# Frequency_Counter_v2.net
KiCad netlist of a schematic drawn in EAGLE
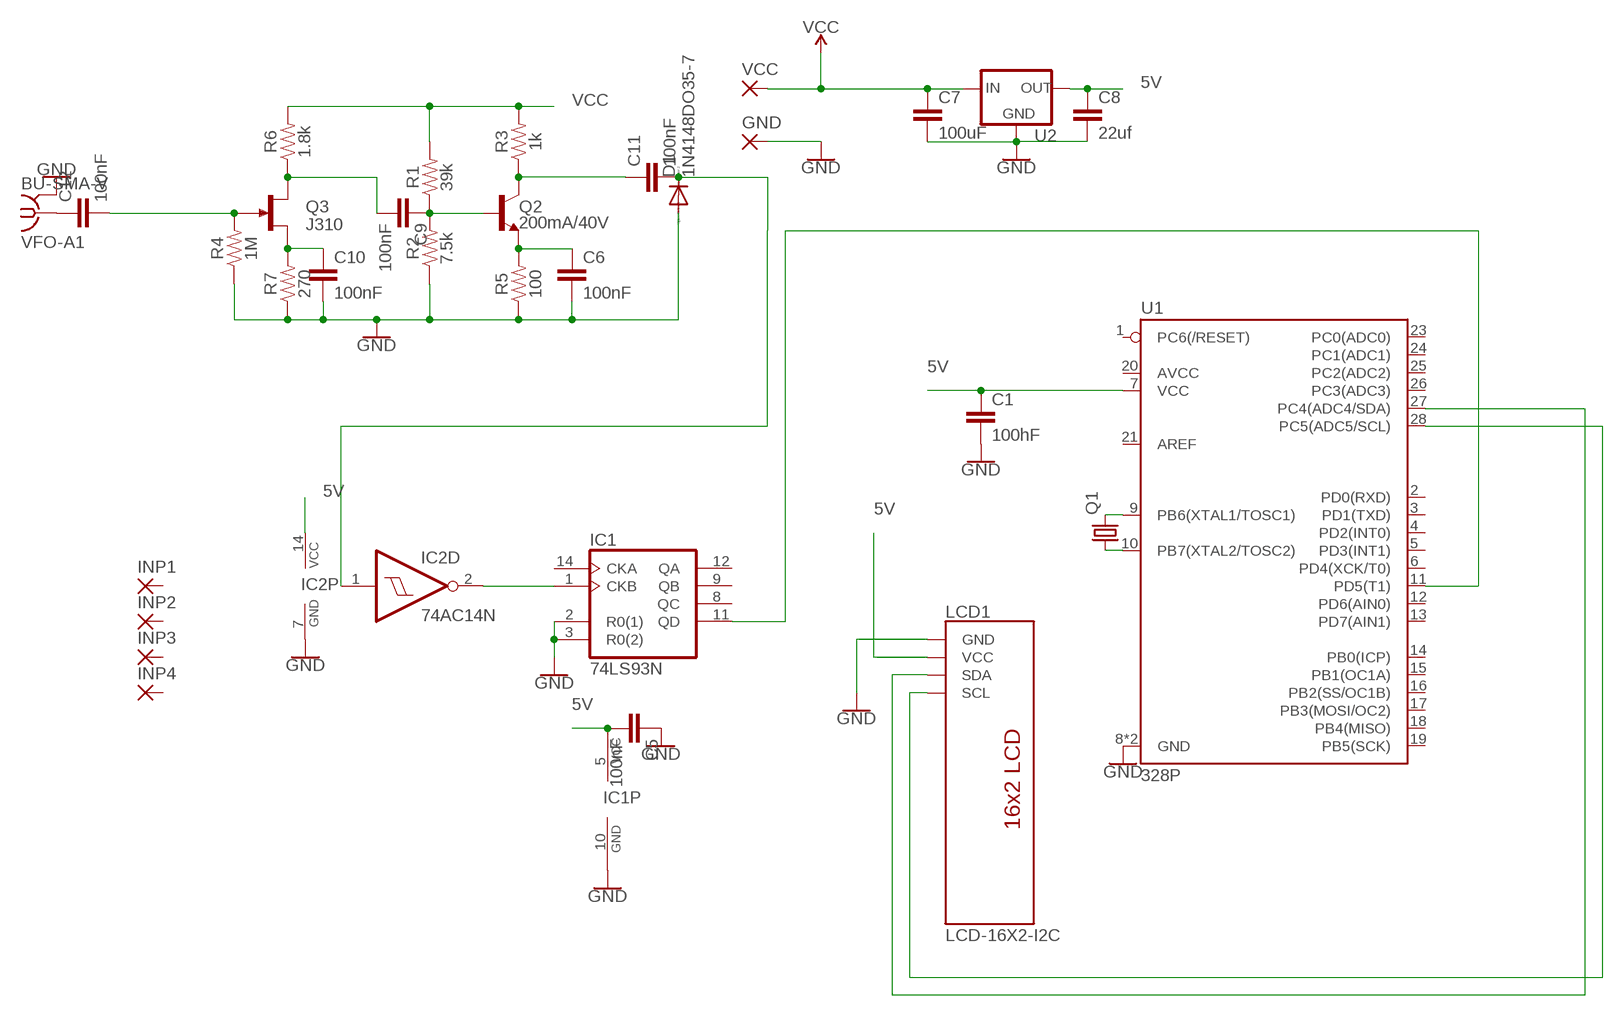
[diagram p0: schematic, sheet 1]

(export (version "E")
  (design (tool "Eeschema 10.0.6"))
  (components
    (comp (ref "C1")
      (value "100hF")
      (footprint "eagle-import:C5B3.5")
      (libsource (lib "eagle-import") (part "C5/3.5"))
    )
    (comp (ref "C5")
      (value "100nF")
      (footprint "eagle-import:C5B3.5")
      (libsource (lib "eagle-import") (part "C5/3.5"))
    )
    (comp (ref "C6")
      (value "100nF")
      (footprint "eagle-import:C5B3.5")
      (libsource (lib "eagle-import") (part "C5/3.5"))
    )
    (comp (ref "C7")
      (value "100uF")
      (footprint "eagle-import:C5B3.5")
      (libsource (lib "eagle-import") (part "C5/3.5"))
    )
    (comp (ref "C8")
      (value "22uf")
      (footprint "eagle-import:C5B3.5")
      (libsource (lib "eagle-import") (part "C5/3.5"))
    )
    (comp (ref "C9")
      (value "100nF")
      (footprint "eagle-import:C5B3.5")
      (libsource (lib "eagle-import") (part "C5/3.5"))
    )
    (comp (ref "C10")
      (value "100nF")
      (footprint "eagle-import:C5B3.5")
      (libsource (lib "eagle-import") (part "C5/3.5"))
    )
    (comp (ref "C11")
      (value "100nF")
      (footprint "eagle-import:C5B3.5")
      (libsource (lib "eagle-import") (part "C5/3.5"))
    )
    (comp (ref "C12")
      (value "100nF")
      (footprint "eagle-import:C5B3.5")
      (libsource (lib "eagle-import") (part "C5/3.5"))
    )
    (comp (ref "D1")
      (value "1N4148DO35-7")
      (footprint "eagle-import:DO35-7")
      (libsource (lib "eagle-import") (part "1N4148DO35-7"))
    )
    (comp (ref "GND")
      (value "3,17/1,1")
      (footprint "eagle-import:3,17_1,1")
      (libsource (lib "eagle-import") (part "3,17/1,1"))
    )
    (comp (ref "IC1")
      (value "74LS93N")
      (footprint "eagle-import:DIL14")
      (libsource (lib "eagle-import") (part "7493NLS"))
    )
    (comp (ref "IC2")
      (value "74AC14N")
      (footprint "eagle-import:DIL14")
      (libsource (lib "eagle-import") (part "7414NAC"))
    )
    (comp (ref "INP1")
      (value "3,17/1,1")
      (footprint "eagle-import:3,17_1,1")
      (libsource (lib "eagle-import") (part "3,17/1,1"))
    )
    (comp (ref "INP2")
      (value "3,17/1,1")
      (footprint "eagle-import:3,17_1,1")
      (libsource (lib "eagle-import") (part "3,17/1,1"))
    )
    (comp (ref "INP3")
      (value "3,17/1,1")
      (footprint "eagle-import:3,17_1,1")
      (libsource (lib "eagle-import") (part "3,17/1,1"))
    )
    (comp (ref "INP4")
      (value "3,17/1,1")
      (footprint "eagle-import:3,17_1,1")
      (libsource (lib "eagle-import") (part "3,17/1,1"))
    )
    (comp (ref "LCD1")
      (value "LCD-16X2-I2C")
      (footprint "eagle-import:LCD-16X2-I2C")
      (libsource (lib "eagle-import") (part "LCD-16X2-I2C"))
    )
    (comp (ref "Q1")
      (value "CRYTALHC49S")
      (footprint "eagle-import:HC49_S")
      (libsource (lib "eagle-import") (part "CRYTALHC49S"))
    )
    (comp (ref "Q2")
      (value "200mA/40V")
      (footprint "eagle-import:TO-92")
      (libsource (lib "eagle-import") (part "TRANS_NPN-2N3904"))
    )
    (comp (ref "Q3")
      (value "J310")
      (footprint "eagle-import:TO92R")
      (libsource (lib "eagle-import") (part "J310"))
    )
    (comp (ref "R1")
      (value "39k")
      (footprint "eagle-import:AXIAL-0.3")
      (libsource (lib "eagle-import") (part "10KOHM-HORIZ-1/4W-1%"))
    )
    (comp (ref "R2")
      (value "7.5k")
      (footprint "eagle-import:AXIAL-0.3")
      (libsource (lib "eagle-import") (part "10KOHM-HORIZ-1/4W-1%"))
    )
    (comp (ref "R3")
      (value "1k")
      (footprint "eagle-import:AXIAL-0.3")
      (libsource (lib "eagle-import") (part "10KOHM-HORIZ-1/4W-1%"))
    )
    (comp (ref "R4")
      (value "1M")
      (footprint "eagle-import:AXIAL-0.3")
      (libsource (lib "eagle-import") (part "10KOHM-HORIZ-1/4W-1%"))
    )
    (comp (ref "R5")
      (value "100")
      (footprint "eagle-import:AXIAL-0.3")
      (libsource (lib "eagle-import") (part "10KOHM-HORIZ-1/4W-1%"))
    )
    (comp (ref "R6")
      (value "1.8k")
      (footprint "eagle-import:AXIAL-0.3")
      (libsource (lib "eagle-import") (part "10KOHM-HORIZ-1/4W-1%"))
    )
    (comp (ref "R7")
      (value "270")
      (footprint "eagle-import:AXIAL-0.3")
      (libsource (lib "eagle-import") (part "10KOHM-HORIZ-1/4W-1%"))
    )
    (comp (ref "U1")
      (value "328P")
      (footprint "eagle-import:DIP28")
      (libsource (lib "eagle-import") (part "ATMEGA328P_PDIP"))
    )
    (comp (ref "U2")
      (value "V_REG_78XXSINK")
      (footprint "eagle-import:TO220-IGO")
      (libsource (lib "eagle-import") (part "V_REG_78XXSINK"))
    )
    (comp (ref "VCC")
      (value "3,17/1,1")
      (footprint "eagle-import:3,17_1,1")
      (libsource (lib "eagle-import") (part "3,17/1,1"))
    )
    (comp (ref "VFO-A1")
      (value "BU-SMA-V")
      (footprint "eagle-import:BU-SMA-V")
      (libsource (lib "eagle-import") (part "BU-SMA-V"))
    )
  )
  (nets
    (net (code "1") (name "/5V") (class "Default")
      (node (ref "C1") (pin "1") (pinfunction "1_1") (pintype "passive"))
      (node (ref "C5") (pin "2") (pinfunction "2_2") (pintype "passive"))
      (node (ref "C8") (pin "1") (pinfunction "1_1") (pintype "passive"))
      (node (ref "IC1") (pin "5") (pinfunction "VCC_5") (pintype "power_in"))
      (node (ref "IC2") (pin "14") (pinfunction "VCC_14") (pintype "power_in"))
      (node (ref "LCD1") (pin "2") (pinfunction "VCC_2") (pintype "power_in"))
      (node (ref "U1") (pin "7") (pinfunction "VCC_7") (pintype "bidirectional"))
      (node (ref "U2") (pin "OUT") (pinfunction "OUT_OUT") (pintype "passive"))
    )
    (net (code "2") (name "GND") (class "Default")
      (node (ref "C1") (pin "2") (pinfunction "2_2") (pintype "passive"))
      (node (ref "C10") (pin "2") (pinfunction "2_2") (pintype "passive"))
      (node (ref "C5") (pin "1") (pinfunction "1_1") (pintype "passive"))
      (node (ref "C6") (pin "2") (pinfunction "2_2") (pintype "passive"))
      (node (ref "C7") (pin "2") (pinfunction "2_2") (pintype "passive"))
      (node (ref "C8") (pin "2") (pinfunction "2_2") (pintype "passive"))
      (node (ref "D1") (pin "A") (pinfunction "A_A") (pintype "passive"))
      (node (ref "GND") (pin "1") (pinfunction "P_1") (pintype "passive"))
      (node (ref "IC1") (pin "10") (pinfunction "GND_10") (pintype "power_in"))
      (node (ref "IC1") (pin "2") (pinfunction "R0(1)_2") (pintype "input"))
      (node (ref "IC1") (pin "3") (pinfunction "R0(2)_3") (pintype "input"))
      (node (ref "IC2") (pin "7") (pinfunction "GND_7") (pintype "power_in"))
      (node (ref "LCD1") (pin "1") (pinfunction "GND_1") (pintype "power_in"))
      (node (ref "R2") (pin "P$1") (pinfunction "1_P$1") (pintype "passive"))
      (node (ref "R4") (pin "P$1") (pinfunction "1_P$1") (pintype "passive"))
      (node (ref "R5") (pin "P$1") (pinfunction "1_P$1") (pintype "passive"))
      (node (ref "R7") (pin "P$1") (pinfunction "1_P$1") (pintype "passive"))
      (node (ref "U1") (pin "22") (pinfunction "GND_22") (pintype "bidirectional"))
      (node (ref "U1") (pin "8") (pinfunction "GND_8") (pintype "bidirectional"))
      (node (ref "U2") (pin "GND") (pinfunction "GND_GND") (pintype "input"))
      (node (ref "VFO-A1") (pin "2") (pinfunction "2_2") (pintype "passive"))
      (node (ref "VFO-A1") (pin "3") (pinfunction "2_3") (pintype "passive"))
      (node (ref "VFO-A1") (pin "4") (pinfunction "2_4") (pintype "passive"))
      (node (ref "VFO-A1") (pin "5") (pinfunction "2_5") (pintype "passive"))
    )
    (net (code "3") (name "Net-(C12-Pad1)") (class "Default")
      (node (ref "C12") (pin "1") (pinfunction "1_1") (pintype "passive"))
      (node (ref "VFO-A1") (pin "1") (pinfunction "1_1") (pintype "passive"))
    )
    (net (code "4") (name "Net-(IC1A-CKB)") (class "Default")
      (node (ref "IC1") (pin "1") (pinfunction "CKB_1") (pintype "input"))
      (node (ref "IC2") (pin "2") (pinfunction "O_2") (pintype "output"))
    )
    (net (code "5") (name "Net-(IC1A-QD)") (class "Default")
      (node (ref "IC1") (pin "11") (pinfunction "QD_11") (pintype "output"))
      (node (ref "U1") (pin "11") (pinfunction "PD5(T1)_11") (pintype "bidirectional"))
    )
    (net (code "6") (name "Net-(IC2D-I)") (class "Default")
      (node (ref "C11") (pin "2") (pinfunction "2_2") (pintype "passive"))
      (node (ref "D1") (pin "C") (pinfunction "C_C") (pintype "passive"))
      (node (ref "IC2") (pin "1") (pinfunction "I_1") (pintype "input"))
    )
    (net (code "7") (name "Net-(LCD1-SCL)") (class "Default")
      (node (ref "LCD1") (pin "4") (pinfunction "SCL_4") (pintype "input"))
      (node (ref "U1") (pin "28") (pinfunction "PC5(ADC5/SCL)_28") (pintype "bidirectional"))
    )
    (net (code "8") (name "Net-(LCD1-SDA)") (class "Default")
      (node (ref "LCD1") (pin "3") (pinfunction "SDA_3") (pintype "bidirectional"))
      (node (ref "U1") (pin "27") (pinfunction "PC4(ADC4/SDA)_27") (pintype "bidirectional"))
    )
    (net (code "9") (name "Net-(Q2-B)") (class "Default")
      (node (ref "C9") (pin "1") (pinfunction "1_1") (pintype "passive"))
      (node (ref "Q2") (pin "2") (pinfunction "B_2") (pintype "passive"))
      (node (ref "R1") (pin "P$1") (pinfunction "1_P$1") (pintype "passive"))
      (node (ref "R2") (pin "P$2") (pinfunction "2_P$2") (pintype "passive"))
    )
    (net (code "10") (name "Net-(Q2-C)") (class "Default")
      (node (ref "C11") (pin "1") (pinfunction "1_1") (pintype "passive"))
      (node (ref "Q2") (pin "3") (pinfunction "C_3") (pintype "passive"))
      (node (ref "R3") (pin "P$1") (pinfunction "1_P$1") (pintype "passive"))
    )
    (net (code "11") (name "Net-(Q2-E)") (class "Default")
      (node (ref "C6") (pin "1") (pinfunction "1_1") (pintype "passive"))
      (node (ref "Q2") (pin "1") (pinfunction "E_1") (pintype "passive"))
      (node (ref "R5") (pin "P$2") (pinfunction "2_P$2") (pintype "passive"))
    )
    (net (code "12") (name "Net-(R4-2)") (class "Default")
      (node (ref "C12") (pin "2") (pinfunction "2_2") (pintype "passive"))
      (node (ref "Q3") (pin "G") (pinfunction "G_G") (pintype "passive"))
      (node (ref "R4") (pin "P$2") (pinfunction "2_P$2") (pintype "passive"))
    )
    (net (code "13") (name "Net-(R6-1)") (class "Default")
      (node (ref "C9") (pin "2") (pinfunction "2_2") (pintype "passive"))
      (node (ref "Q3") (pin "D") (pinfunction "D_D") (pintype "passive"))
      (node (ref "R6") (pin "P$1") (pinfunction "1_P$1") (pintype "passive"))
    )
    (net (code "14") (name "Net-(R7-2)") (class "Default")
      (node (ref "C10") (pin "1") (pinfunction "1_1") (pintype "passive"))
      (node (ref "Q3") (pin "S") (pinfunction "S_S") (pintype "passive"))
      (node (ref "R7") (pin "P$2") (pinfunction "2_P$2") (pintype "passive"))
    )
    (net (code "15") (name "Net-(U1-PB6(XTAL1{slash}TOSC1))") (class "Default")
      (node (ref "Q1") (pin "2") (pinfunction "2_2") (pintype "passive"))
      (node (ref "U1") (pin "9") (pinfunction "PB6(XTAL1/TOSC1)_9") (pintype "bidirectional"))
    )
    (net (code "16") (name "Net-(U1-PB7(XTAL2{slash}TOSC2))") (class "Default")
      (node (ref "Q1") (pin "1") (pinfunction "1_1") (pintype "passive"))
      (node (ref "U1") (pin "10") (pinfunction "PB7(XTAL2/TOSC2)_10") (pintype "bidirectional"))
    )
    (net (code "17") (name "VCC") (class "Default")
      (node (ref "C7") (pin "1") (pinfunction "1_1") (pintype "passive"))
      (node (ref "R1") (pin "P$2") (pinfunction "2_P$2") (pintype "passive"))
      (node (ref "R3") (pin "P$2") (pinfunction "2_P$2") (pintype "passive"))
      (node (ref "R6") (pin "P$2") (pinfunction "2_P$2") (pintype "passive"))
      (node (ref "U2") (pin "IN") (pinfunction "IN_IN") (pintype "input"))
      (node (ref "VCC") (pin "1") (pinfunction "P_1") (pintype "passive"))
    )
    (net (code "18") (name "unconnected-(IC1A-CKA-Pad14)") (class "Default")
      (node (ref "IC1") (pin "14") (pinfunction "CKA_14") (pintype "input"))
    )
    (net (code "19") (name "unconnected-(IC1A-QA-Pad12)") (class "Default")
      (node (ref "IC1") (pin "12") (pinfunction "QA_12") (pintype "output"))
    )
    (net (code "20") (name "unconnected-(IC1A-QB-Pad9)") (class "Default")
      (node (ref "IC1") (pin "9") (pinfunction "QB_9") (pintype "output"))
    )
    (net (code "21") (name "unconnected-(IC1A-QC-Pad8)") (class "Default")
      (node (ref "IC1") (pin "8") (pinfunction "QC_8") (pintype "output"))
    )
    (net (code "22") (name "unconnected-(INP1-P-Pad1)") (class "Default")
      (node (ref "INP1") (pin "1") (pinfunction "P_1") (pintype "passive"))
    )
    (net (code "23") (name "unconnected-(INP2-P-Pad1)") (class "Default")
      (node (ref "INP2") (pin "1") (pinfunction "P_1") (pintype "passive"))
    )
    (net (code "24") (name "unconnected-(INP3-P-Pad1)") (class "Default")
      (node (ref "INP3") (pin "1") (pinfunction "P_1") (pintype "passive"))
    )
    (net (code "25") (name "unconnected-(INP4-P-Pad1)") (class "Default")
      (node (ref "INP4") (pin "1") (pinfunction "P_1") (pintype "passive"))
    )
    (net (code "26") (name "unconnected-(U1-AREF-Pad21)") (class "Default")
      (node (ref "U1") (pin "21") (pinfunction "AREF_21") (pintype "bidirectional"))
    )
    (net (code "27") (name "unconnected-(U1-AVCC-Pad20)") (class "Default")
      (node (ref "U1") (pin "20") (pinfunction "AVCC_20") (pintype "bidirectional"))
    )
    (net (code "28") (name "unconnected-(U1-PB0(ICP)-Pad14)") (class "Default")
      (node (ref "U1") (pin "14") (pinfunction "PB0(ICP)_14") (pintype "bidirectional"))
    )
    (net (code "29") (name "unconnected-(U1-PB1(OC1A)-Pad15)") (class "Default")
      (node (ref "U1") (pin "15") (pinfunction "PB1(OC1A)_15") (pintype "bidirectional"))
    )
    (net (code "30") (name "unconnected-(U1-PB2(SS{slash}OC1B)-Pad16)") (class "Default")
      (node (ref "U1") (pin "16") (pinfunction "PB2(SS/OC1B)_16") (pintype "bidirectional"))
    )
    (net (code "31") (name "unconnected-(U1-PB3(MOSI{slash}OC2)-Pad17)") (class "Default")
      (node (ref "U1") (pin "17") (pinfunction "PB3(MOSI/OC2)_17") (pintype "bidirectional"))
    )
    (net (code "32") (name "unconnected-(U1-PB4(MISO)-Pad18)") (class "Default")
      (node (ref "U1") (pin "18") (pinfunction "PB4(MISO)_18") (pintype "bidirectional"))
    )
    (net (code "33") (name "unconnected-(U1-PB5(SCK)-Pad19)") (class "Default")
      (node (ref "U1") (pin "19") (pinfunction "PB5(SCK)_19") (pintype "bidirectional"))
    )
    (net (code "34") (name "unconnected-(U1-PC0(ADC0)-Pad23)") (class "Default")
      (node (ref "U1") (pin "23") (pinfunction "PC0(ADC0)_23") (pintype "bidirectional"))
    )
    (net (code "35") (name "unconnected-(U1-PC1(ADC1)-Pad24)") (class "Default")
      (node (ref "U1") (pin "24") (pinfunction "PC1(ADC1)_24") (pintype "bidirectional"))
    )
    (net (code "36") (name "unconnected-(U1-PC2(ADC2)-Pad25)") (class "Default")
      (node (ref "U1") (pin "25") (pinfunction "PC2(ADC2)_25") (pintype "bidirectional"))
    )
    (net (code "37") (name "unconnected-(U1-PC3(ADC3)-Pad26)") (class "Default")
      (node (ref "U1") (pin "26") (pinfunction "PC3(ADC3)_26") (pintype "bidirectional"))
    )
    (net (code "38") (name "unconnected-(U1-PC6({slash}RESET)-Pad1)") (class "Default")
      (node (ref "U1") (pin "1") (pinfunction "PC6(/RESET)_1") (pintype "bidirectional"))
    )
    (net (code "39") (name "unconnected-(U1-PD0(RXD)-Pad2)") (class "Default")
      (node (ref "U1") (pin "2") (pinfunction "PD0(RXD)_2") (pintype "bidirectional"))
    )
    (net (code "40") (name "unconnected-(U1-PD1(TXD)-Pad3)") (class "Default")
      (node (ref "U1") (pin "3") (pinfunction "PD1(TXD)_3") (pintype "bidirectional"))
    )
    (net (code "41") (name "unconnected-(U1-PD2(INT0)-Pad4)") (class "Default")
      (node (ref "U1") (pin "4") (pinfunction "PD2(INT0)_4") (pintype "bidirectional"))
    )
    (net (code "42") (name "unconnected-(U1-PD3(INT1)-Pad5)") (class "Default")
      (node (ref "U1") (pin "5") (pinfunction "PD3(INT1)_5") (pintype "bidirectional"))
    )
    (net (code "43") (name "unconnected-(U1-PD4(XCK{slash}T0)-Pad6)") (class "Default")
      (node (ref "U1") (pin "6") (pinfunction "PD4(XCK/T0)_6") (pintype "bidirectional"))
    )
    (net (code "44") (name "unconnected-(U1-PD6(AIN0)-Pad12)") (class "Default")
      (node (ref "U1") (pin "12") (pinfunction "PD6(AIN0)_12") (pintype "bidirectional"))
    )
    (net (code "45") (name "unconnected-(U1-PD7(AIN1)-Pad13)") (class "Default")
      (node (ref "U1") (pin "13") (pinfunction "PD7(AIN1)_13") (pintype "bidirectional"))
    )
  )
)
